# FanController.net
KiCad netlist of a schematic drawn in EAGLE
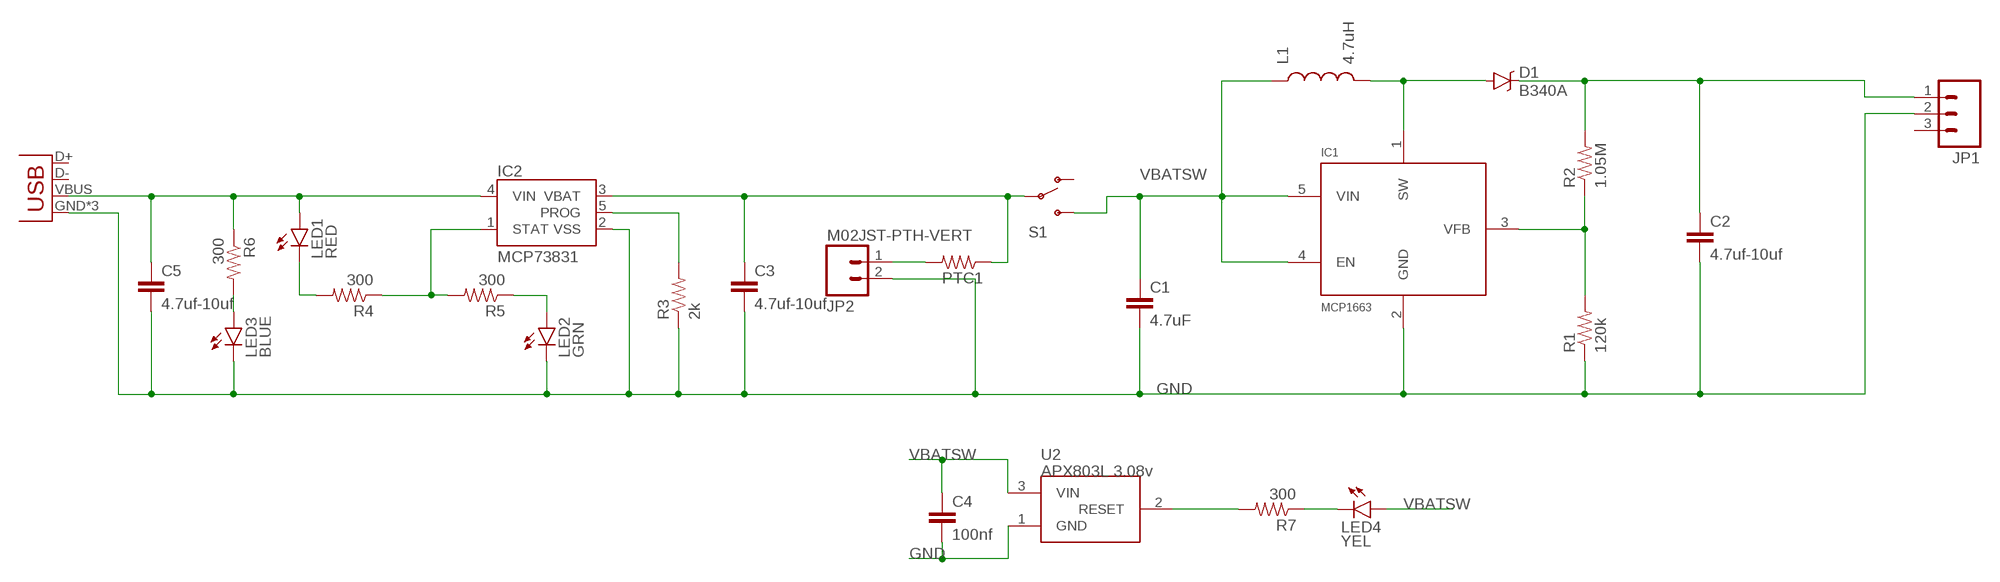
[diagram p0: schematic, sheet 1]

(export (version "E")
  (design (tool "Eeschema 10.0.6"))
  (components
    (comp (ref "C1")
      (value "4.7uF")
      (footprint "eagle-import:1206")
      (libsource (lib "eagle-import") (part "CAP1206"))
    )
    (comp (ref "C2")
      (value "4.7uf-10uf")
      (footprint "eagle-import:1206")
      (libsource (lib "eagle-import") (part "CAP1206"))
    )
    (comp (ref "C3")
      (value "4.7uf-10uf")
      (footprint "eagle-import:1206")
      (libsource (lib "eagle-import") (part "CAP1206"))
    )
    (comp (ref "C4")
      (value "100nf")
      (footprint "eagle-import:1206")
      (libsource (lib "eagle-import") (part "CAP1206"))
    )
    (comp (ref "C5")
      (value "4.7uf-10uf")
      (footprint "eagle-import:1206")
      (libsource (lib "eagle-import") (part "CAP1206"))
    )
    (comp (ref "D1")
      (value "B340A")
      (footprint "eagle-import:SMA-DIODE")
      (libsource (lib "eagle-import") (part "DIODE-SCHOTTKY-B340A"))
    )
    (comp (ref "IC1")
      (value "MCP1663")
      (footprint "eagle-import:SOT23-5")
      (libsource (lib "eagle-import") (part "MCP1663"))
    )
    (comp (ref "IC2")
      (value "MCP73831")
      (footprint "eagle-import:SOT23-5")
      (libsource (lib "eagle-import") (part "MCP73831"))
    )
    (comp (ref "JP1")
      (value "M03POLAR_LOCK")
      (footprint "eagle-import:MOLEX-1X3_LOCK")
      (libsource (lib "eagle-import") (part "M03POLAR_LOCK"))
    )
    (comp (ref "JP2")
      (value "M02JST-PTH-VERT")
      (footprint "eagle-import:JST-2-PTH-VERT")
      (libsource (lib "eagle-import") (part "M02JST-PTH-VERT"))
    )
    (comp (ref "JP3")
      (value "USB-MICROB")
      (footprint "eagle-import:USB-MICROB")
      (libsource (lib "eagle-import") (part "USB-MICROB"))
    )
    (comp (ref "L1")
      (value "4.7uH")
      (footprint "eagle-import:1210")
      (libsource (lib "eagle-import") (part "INDUCTOR1210"))
    )
    (comp (ref "LED1")
      (value "RED")
      (footprint "eagle-import:LED-1206")
      (libsource (lib "eagle-import") (part "LED1206"))
    )
    (comp (ref "LED2")
      (value "GRN")
      (footprint "eagle-import:LED-1206")
      (libsource (lib "eagle-import") (part "LED1206"))
    )
    (comp (ref "LED3")
      (value "BLUE")
      (footprint "eagle-import:LED-1206")
      (libsource (lib "eagle-import") (part "LED1206"))
    )
    (comp (ref "LED4")
      (value "YEL")
      (footprint "eagle-import:LED-1206")
      (libsource (lib "eagle-import") (part "LED1206"))
    )
    (comp (ref "PTC1")
      (value "RESISTOR1206")
      (footprint "eagle-import:1206")
      (libsource (lib "eagle-import") (part "RESISTOR1206"))
    )
    (comp (ref "R1")
      (value "120k")
      (footprint "eagle-import:1206")
      (libsource (lib "eagle-import") (part "RESISTOR1206"))
    )
    (comp (ref "R2")
      (value "1.05M")
      (footprint "eagle-import:1206")
      (libsource (lib "eagle-import") (part "RESISTOR1206"))
    )
    (comp (ref "R3")
      (value "2k")
      (footprint "eagle-import:1206")
      (libsource (lib "eagle-import") (part "RESISTOR1206"))
    )
    (comp (ref "R4")
      (value "300")
      (footprint "eagle-import:1206")
      (libsource (lib "eagle-import") (part "RESISTOR1206"))
    )
    (comp (ref "R5")
      (value "300")
      (footprint "eagle-import:1206")
      (libsource (lib "eagle-import") (part "RESISTOR1206"))
    )
    (comp (ref "R6")
      (value "300")
      (footprint "eagle-import:1206")
      (libsource (lib "eagle-import") (part "RESISTOR1206"))
    )
    (comp (ref "R7")
      (value "300")
      (footprint "eagle-import:1206")
      (libsource (lib "eagle-import") (part "RESISTOR1206"))
    )
    (comp (ref "S1")
      (value "SWITCH-SPDTKIT")
      (footprint "eagle-import:SWITCH-SPDT_KIT")
      (libsource (lib "eagle-import") (part "SWITCH-SPDTKIT"))
    )
    (comp (ref "U2")
      (value "APX803L 3.08v")
      (footprint "eagle-import:SOT23")
      (libsource (lib "eagle-import") (part "ADP160"))
    )
  )
  (nets
    (net (code "1") (name "/GND") (class "Default")
      (node (ref "C1") (pin "2") (pinfunction "2_2") (pintype "passive"))
      (node (ref "C2") (pin "2") (pinfunction "2_2") (pintype "passive"))
      (node (ref "C3") (pin "2") (pinfunction "2_2") (pintype "passive"))
      (node (ref "C4") (pin "2") (pinfunction "2_2") (pintype "passive"))
      (node (ref "C5") (pin "2") (pinfunction "2_2") (pintype "passive"))
      (node (ref "IC1") (pin "2") (pinfunction "GND_2") (pintype "bidirectional"))
      (node (ref "IC2") (pin "2") (pinfunction "VSS_2") (pintype "power_in"))
      (node (ref "JP1") (pin "2") (pinfunction "2_2") (pintype "passive"))
      (node (ref "JP2") (pin "2") (pinfunction "2_2") (pintype "passive"))
      (node (ref "JP3") (pin "GND") (pinfunction "GND_GND") (pintype "bidirectional"))
      (node (ref "JP3") (pin "MT1") (pinfunction "GND_MT1") (pintype "bidirectional"))
      (node (ref "JP3") (pin "MT2") (pinfunction "GND_MT2") (pintype "bidirectional"))
      (node (ref "LED2") (pin "C") (pinfunction "C_C") (pintype "passive"))
      (node (ref "LED3") (pin "C") (pinfunction "C_C") (pintype "passive"))
      (node (ref "R1") (pin "1") (pinfunction "1_1") (pintype "passive"))
      (node (ref "R3") (pin "1") (pinfunction "1_1") (pintype "passive"))
      (node (ref "U2") (pin "1") (pinfunction "GND_1") (pintype "bidirectional"))
    )
    (net (code "2") (name "/VBATSW") (class "Default")
      (node (ref "C1") (pin "1") (pinfunction "1_1") (pintype "passive"))
      (node (ref "C4") (pin "1") (pinfunction "1_1") (pintype "passive"))
      (node (ref "IC1") (pin "4") (pinfunction "EN_4") (pintype "bidirectional"))
      (node (ref "IC1") (pin "5") (pinfunction "VIN_5") (pintype "bidirectional"))
      (node (ref "L1") (pin "1") (pinfunction "1_1") (pintype "passive"))
      (node (ref "LED4") (pin "A") (pinfunction "A_A") (pintype "passive"))
      (node (ref "S1") (pin "3") (pinfunction "S_3") (pintype "passive"))
      (node (ref "U2") (pin "3") (pinfunction "VIN_3") (pintype "bidirectional"))
    )
    (net (code "3") (name "Net-(C2-Pad1)") (class "Default")
      (node (ref "C2") (pin "1") (pinfunction "1_1") (pintype "passive"))
      (node (ref "D1") (pin "C") (pinfunction "C_C") (pintype "passive"))
      (node (ref "JP1") (pin "1") (pinfunction "1_1") (pintype "passive"))
      (node (ref "R2") (pin "2") (pinfunction "2_2") (pintype "passive"))
    )
    (net (code "4") (name "Net-(IC1-SW)") (class "Default")
      (node (ref "D1") (pin "A") (pinfunction "A_A") (pintype "passive"))
      (node (ref "IC1") (pin "1") (pinfunction "SW_1") (pintype "bidirectional"))
      (node (ref "L1") (pin "2") (pinfunction "2_2") (pintype "passive"))
    )
    (net (code "5") (name "Net-(IC1-VFB)") (class "Default")
      (node (ref "IC1") (pin "3") (pinfunction "VFB_3") (pintype "bidirectional"))
      (node (ref "R1") (pin "2") (pinfunction "2_2") (pintype "passive"))
      (node (ref "R2") (pin "1") (pinfunction "1_1") (pintype "passive"))
    )
    (net (code "6") (name "Net-(IC2-PROG)") (class "Default")
      (node (ref "IC2") (pin "5") (pinfunction "PROG_5") (pintype "input"))
      (node (ref "R3") (pin "2") (pinfunction "2_2") (pintype "passive"))
    )
    (net (code "7") (name "Net-(IC2-STAT)") (class "Default")
      (node (ref "IC2") (pin "1") (pinfunction "STAT_1") (pintype "output"))
      (node (ref "R4") (pin "1") (pinfunction "1_1") (pintype "passive"))
      (node (ref "R5") (pin "2") (pinfunction "2_2") (pintype "passive"))
    )
    (net (code "8") (name "Net-(IC2-VBAT)") (class "Default")
      (node (ref "C3") (pin "1") (pinfunction "1_1") (pintype "passive"))
      (node (ref "IC2") (pin "3") (pinfunction "VBAT_3") (pintype "power_in"))
      (node (ref "PTC1") (pin "1") (pinfunction "1_1") (pintype "passive"))
      (node (ref "S1") (pin "2") (pinfunction "P_2") (pintype "passive"))
    )
    (net (code "9") (name "Net-(IC2-VIN)") (class "Default")
      (node (ref "C5") (pin "1") (pinfunction "1_1") (pintype "passive"))
      (node (ref "IC2") (pin "4") (pinfunction "VIN_4") (pintype "power_in"))
      (node (ref "JP3") (pin "VBUS") (pinfunction "VBUS_VBUS") (pintype "bidirectional"))
      (node (ref "LED1") (pin "A") (pinfunction "A_A") (pintype "passive"))
      (node (ref "R6") (pin "1") (pinfunction "1_1") (pintype "passive"))
    )
    (net (code "10") (name "Net-(JP2-Pad1)") (class "Default")
      (node (ref "JP2") (pin "1") (pinfunction "1_1") (pintype "passive"))
      (node (ref "PTC1") (pin "2") (pinfunction "2_2") (pintype "passive"))
    )
    (net (code "11") (name "Net-(LED1-PadC)") (class "Default")
      (node (ref "LED1") (pin "C") (pinfunction "C_C") (pintype "passive"))
      (node (ref "R4") (pin "2") (pinfunction "2_2") (pintype "passive"))
    )
    (net (code "12") (name "Net-(LED2-PadA)") (class "Default")
      (node (ref "LED2") (pin "A") (pinfunction "A_A") (pintype "passive"))
      (node (ref "R5") (pin "1") (pinfunction "1_1") (pintype "passive"))
    )
    (net (code "13") (name "Net-(LED3-PadA)") (class "Default")
      (node (ref "LED3") (pin "A") (pinfunction "A_A") (pintype "passive"))
      (node (ref "R6") (pin "2") (pinfunction "2_2") (pintype "passive"))
    )
    (net (code "14") (name "Net-(LED4-PadC)") (class "Default")
      (node (ref "LED4") (pin "C") (pinfunction "C_C") (pintype "passive"))
      (node (ref "R7") (pin "1") (pinfunction "1_1") (pintype "passive"))
    )
    (net (code "15") (name "Net-(U2-RESET)") (class "Default")
      (node (ref "R7") (pin "2") (pinfunction "2_2") (pintype "passive"))
      (node (ref "U2") (pin "2") (pinfunction "RESET_2") (pintype "bidirectional"))
    )
    (net (code "16") (name "unconnected-(JP1-Pad3)") (class "Default")
      (node (ref "JP1") (pin "3") (pinfunction "3_3") (pintype "passive"))
    )
    (net (code "17") (name "unconnected-(JP3-PadD+)") (class "Default")
      (node (ref "JP3") (pin "D+") (pinfunction "D+_D+") (pintype "bidirectional"))
    )
    (net (code "18") (name "unconnected-(JP3-PadD-)") (class "Default")
      (node (ref "JP3") (pin "D-") (pinfunction "D-_D-") (pintype "bidirectional"))
    )
    (net (code "19") (name "unconnected-(S1-O-Pad1)") (class "Default")
      (node (ref "S1") (pin "1") (pinfunction "O_1") (pintype "passive"))
    )
  )
)
